# breakout_schematic.net
KiCad netlist of a schematic drawn in Altium Designer
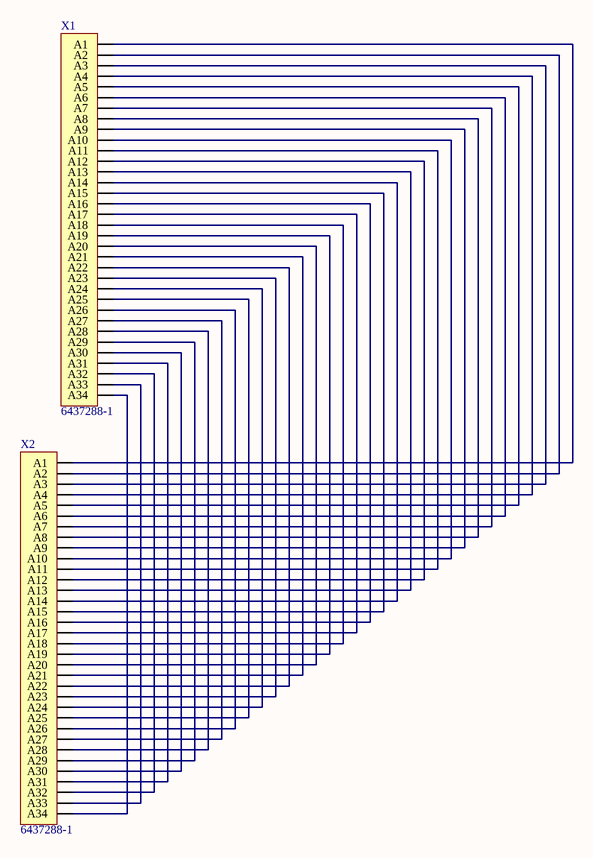
[diagram p0: breakout schematic.SchDoc]

(export (version "E")
  (design (tool "Eeschema 10.0.6"))
  (components
    (comp (ref "X1")
      (value "6437288-1")
      (footprint "6437288-1")
      (description "Superseal 34P")
      (libsource (lib "Connectors") (part "6437288-1"))
    )
    (comp (ref "X2")
      (value "6437288-1")
      (footprint "6437288-1")
      (description "Superseal 34P")
      (libsource (lib "Connectors") (part "6437288-1"))
    )
  )
  (nets
    (net (code "1") (name "Net-(X1-PadA1)") (class "Default")
      (node (ref "X1") (pin "A1") (pinfunction "A1_A1") (pintype "passive"))
      (node (ref "X2") (pin "A1") (pinfunction "A1_A1") (pintype "passive"))
    )
    (net (code "2") (name "Net-(X1-PadA2)") (class "Default")
      (node (ref "X1") (pin "A2") (pinfunction "A2_A2") (pintype "passive"))
      (node (ref "X2") (pin "A2") (pinfunction "A2_A2") (pintype "passive"))
    )
    (net (code "3") (name "Net-(X1-PadA3)") (class "Default")
      (node (ref "X1") (pin "A3") (pinfunction "A3_A3") (pintype "passive"))
      (node (ref "X2") (pin "A3") (pinfunction "A3_A3") (pintype "passive"))
    )
    (net (code "4") (name "Net-(X1-PadA4)") (class "Default")
      (node (ref "X1") (pin "A4") (pinfunction "A4_A4") (pintype "passive"))
      (node (ref "X2") (pin "A4") (pinfunction "A4_A4") (pintype "passive"))
    )
    (net (code "5") (name "Net-(X1-PadA5)") (class "Default")
      (node (ref "X1") (pin "A5") (pinfunction "A5_A5") (pintype "passive"))
      (node (ref "X2") (pin "A5") (pinfunction "A5_A5") (pintype "passive"))
    )
    (net (code "6") (name "Net-(X1-PadA6)") (class "Default")
      (node (ref "X1") (pin "A6") (pinfunction "A6_A6") (pintype "passive"))
      (node (ref "X2") (pin "A6") (pinfunction "A6_A6") (pintype "passive"))
    )
    (net (code "7") (name "Net-(X1-PadA7)") (class "Default")
      (node (ref "X1") (pin "A7") (pinfunction "A7_A7") (pintype "passive"))
      (node (ref "X2") (pin "A7") (pinfunction "A7_A7") (pintype "passive"))
    )
    (net (code "8") (name "Net-(X1-PadA8)") (class "Default")
      (node (ref "X1") (pin "A8") (pinfunction "A8_A8") (pintype "passive"))
      (node (ref "X2") (pin "A8") (pinfunction "A8_A8") (pintype "passive"))
    )
    (net (code "9") (name "Net-(X1-PadA9)") (class "Default")
      (node (ref "X1") (pin "A9") (pinfunction "A9_A9") (pintype "passive"))
      (node (ref "X2") (pin "A9") (pinfunction "A9_A9") (pintype "passive"))
    )
    (net (code "10") (name "Net-(X1-PadA10)") (class "Default")
      (node (ref "X1") (pin "A10") (pinfunction "A10_A10") (pintype "passive"))
      (node (ref "X2") (pin "A10") (pinfunction "A10_A10") (pintype "passive"))
    )
    (net (code "11") (name "Net-(X1-PadA11)") (class "Default")
      (node (ref "X1") (pin "A11") (pinfunction "A11_A11") (pintype "passive"))
      (node (ref "X2") (pin "A11") (pinfunction "A11_A11") (pintype "passive"))
    )
    (net (code "12") (name "Net-(X1-PadA12)") (class "Default")
      (node (ref "X1") (pin "A12") (pinfunction "A12_A12") (pintype "passive"))
      (node (ref "X2") (pin "A12") (pinfunction "A12_A12") (pintype "passive"))
    )
    (net (code "13") (name "Net-(X1-PadA13)") (class "Default")
      (node (ref "X1") (pin "A13") (pinfunction "A13_A13") (pintype "passive"))
      (node (ref "X2") (pin "A13") (pinfunction "A13_A13") (pintype "passive"))
    )
    (net (code "14") (name "Net-(X1-PadA14)") (class "Default")
      (node (ref "X1") (pin "A14") (pinfunction "A14_A14") (pintype "passive"))
      (node (ref "X2") (pin "A14") (pinfunction "A14_A14") (pintype "passive"))
    )
    (net (code "15") (name "Net-(X1-PadA15)") (class "Default")
      (node (ref "X1") (pin "A15") (pinfunction "A15_A15") (pintype "passive"))
      (node (ref "X2") (pin "A15") (pinfunction "A15_A15") (pintype "passive"))
    )
    (net (code "16") (name "Net-(X1-PadA16)") (class "Default")
      (node (ref "X1") (pin "A16") (pinfunction "A16_A16") (pintype "passive"))
      (node (ref "X2") (pin "A16") (pinfunction "A16_A16") (pintype "passive"))
    )
    (net (code "17") (name "Net-(X1-PadA17)") (class "Default")
      (node (ref "X1") (pin "A17") (pinfunction "A17_A17") (pintype "passive"))
      (node (ref "X2") (pin "A17") (pinfunction "A17_A17") (pintype "passive"))
    )
    (net (code "18") (name "Net-(X1-PadA18)") (class "Default")
      (node (ref "X1") (pin "A18") (pinfunction "A18_A18") (pintype "passive"))
      (node (ref "X2") (pin "A18") (pinfunction "A18_A18") (pintype "passive"))
    )
    (net (code "19") (name "Net-(X1-PadA19)") (class "Default")
      (node (ref "X1") (pin "A19") (pinfunction "A19_A19") (pintype "passive"))
      (node (ref "X2") (pin "A19") (pinfunction "A19_A19") (pintype "passive"))
    )
    (net (code "20") (name "Net-(X1-PadA20)") (class "Default")
      (node (ref "X1") (pin "A20") (pinfunction "A20_A20") (pintype "passive"))
      (node (ref "X2") (pin "A20") (pinfunction "A20_A20") (pintype "passive"))
    )
    (net (code "21") (name "Net-(X1-PadA21)") (class "Default")
      (node (ref "X1") (pin "A21") (pinfunction "A21_A21") (pintype "passive"))
      (node (ref "X2") (pin "A21") (pinfunction "A21_A21") (pintype "passive"))
    )
    (net (code "22") (name "Net-(X1-PadA22)") (class "Default")
      (node (ref "X1") (pin "A22") (pinfunction "A22_A22") (pintype "passive"))
      (node (ref "X2") (pin "A22") (pinfunction "A22_A22") (pintype "passive"))
    )
    (net (code "23") (name "Net-(X1-PadA23)") (class "Default")
      (node (ref "X1") (pin "A23") (pinfunction "A23_A23") (pintype "passive"))
      (node (ref "X2") (pin "A23") (pinfunction "A23_A23") (pintype "passive"))
    )
    (net (code "24") (name "Net-(X1-PadA24)") (class "Default")
      (node (ref "X1") (pin "A24") (pinfunction "A24_A24") (pintype "passive"))
      (node (ref "X2") (pin "A24") (pinfunction "A24_A24") (pintype "passive"))
    )
    (net (code "25") (name "Net-(X1-PadA25)") (class "Default")
      (node (ref "X1") (pin "A25") (pinfunction "A25_A25") (pintype "passive"))
      (node (ref "X2") (pin "A25") (pinfunction "A25_A25") (pintype "passive"))
    )
    (net (code "26") (name "Net-(X1-PadA26)") (class "Default")
      (node (ref "X1") (pin "A26") (pinfunction "A26_A26") (pintype "passive"))
      (node (ref "X2") (pin "A26") (pinfunction "A26_A26") (pintype "passive"))
    )
    (net (code "27") (name "Net-(X1-PadA27)") (class "Default")
      (node (ref "X1") (pin "A27") (pinfunction "A27_A27") (pintype "passive"))
      (node (ref "X2") (pin "A27") (pinfunction "A27_A27") (pintype "passive"))
    )
    (net (code "28") (name "Net-(X1-PadA28)") (class "Default")
      (node (ref "X1") (pin "A28") (pinfunction "A28_A28") (pintype "passive"))
      (node (ref "X2") (pin "A28") (pinfunction "A28_A28") (pintype "passive"))
    )
    (net (code "29") (name "Net-(X1-PadA29)") (class "Default")
      (node (ref "X1") (pin "A29") (pinfunction "A29_A29") (pintype "passive"))
      (node (ref "X2") (pin "A29") (pinfunction "A29_A29") (pintype "passive"))
    )
    (net (code "30") (name "Net-(X1-PadA30)") (class "Default")
      (node (ref "X1") (pin "A30") (pinfunction "A30_A30") (pintype "passive"))
      (node (ref "X2") (pin "A30") (pinfunction "A30_A30") (pintype "passive"))
    )
    (net (code "31") (name "Net-(X1-PadA31)") (class "Default")
      (node (ref "X1") (pin "A31") (pinfunction "A31_A31") (pintype "passive"))
      (node (ref "X2") (pin "A31") (pinfunction "A31_A31") (pintype "passive"))
    )
    (net (code "32") (name "Net-(X1-PadA32)") (class "Default")
      (node (ref "X1") (pin "A32") (pinfunction "A32_A32") (pintype "passive"))
      (node (ref "X2") (pin "A32") (pinfunction "A32_A32") (pintype "passive"))
    )
    (net (code "33") (name "Net-(X1-PadA33)") (class "Default")
      (node (ref "X1") (pin "A33") (pinfunction "A33_A33") (pintype "passive"))
      (node (ref "X2") (pin "A33") (pinfunction "A33_A33") (pintype "passive"))
    )
    (net (code "34") (name "Net-(X1-PadA34)") (class "Default")
      (node (ref "X1") (pin "A34") (pinfunction "A34_A34") (pintype "passive"))
      (node (ref "X2") (pin "A34") (pinfunction "A34_A34") (pintype "passive"))
    )
  )
)
